# PiZero2.net
KiCad netlist of a schematic drawn in EAGLE
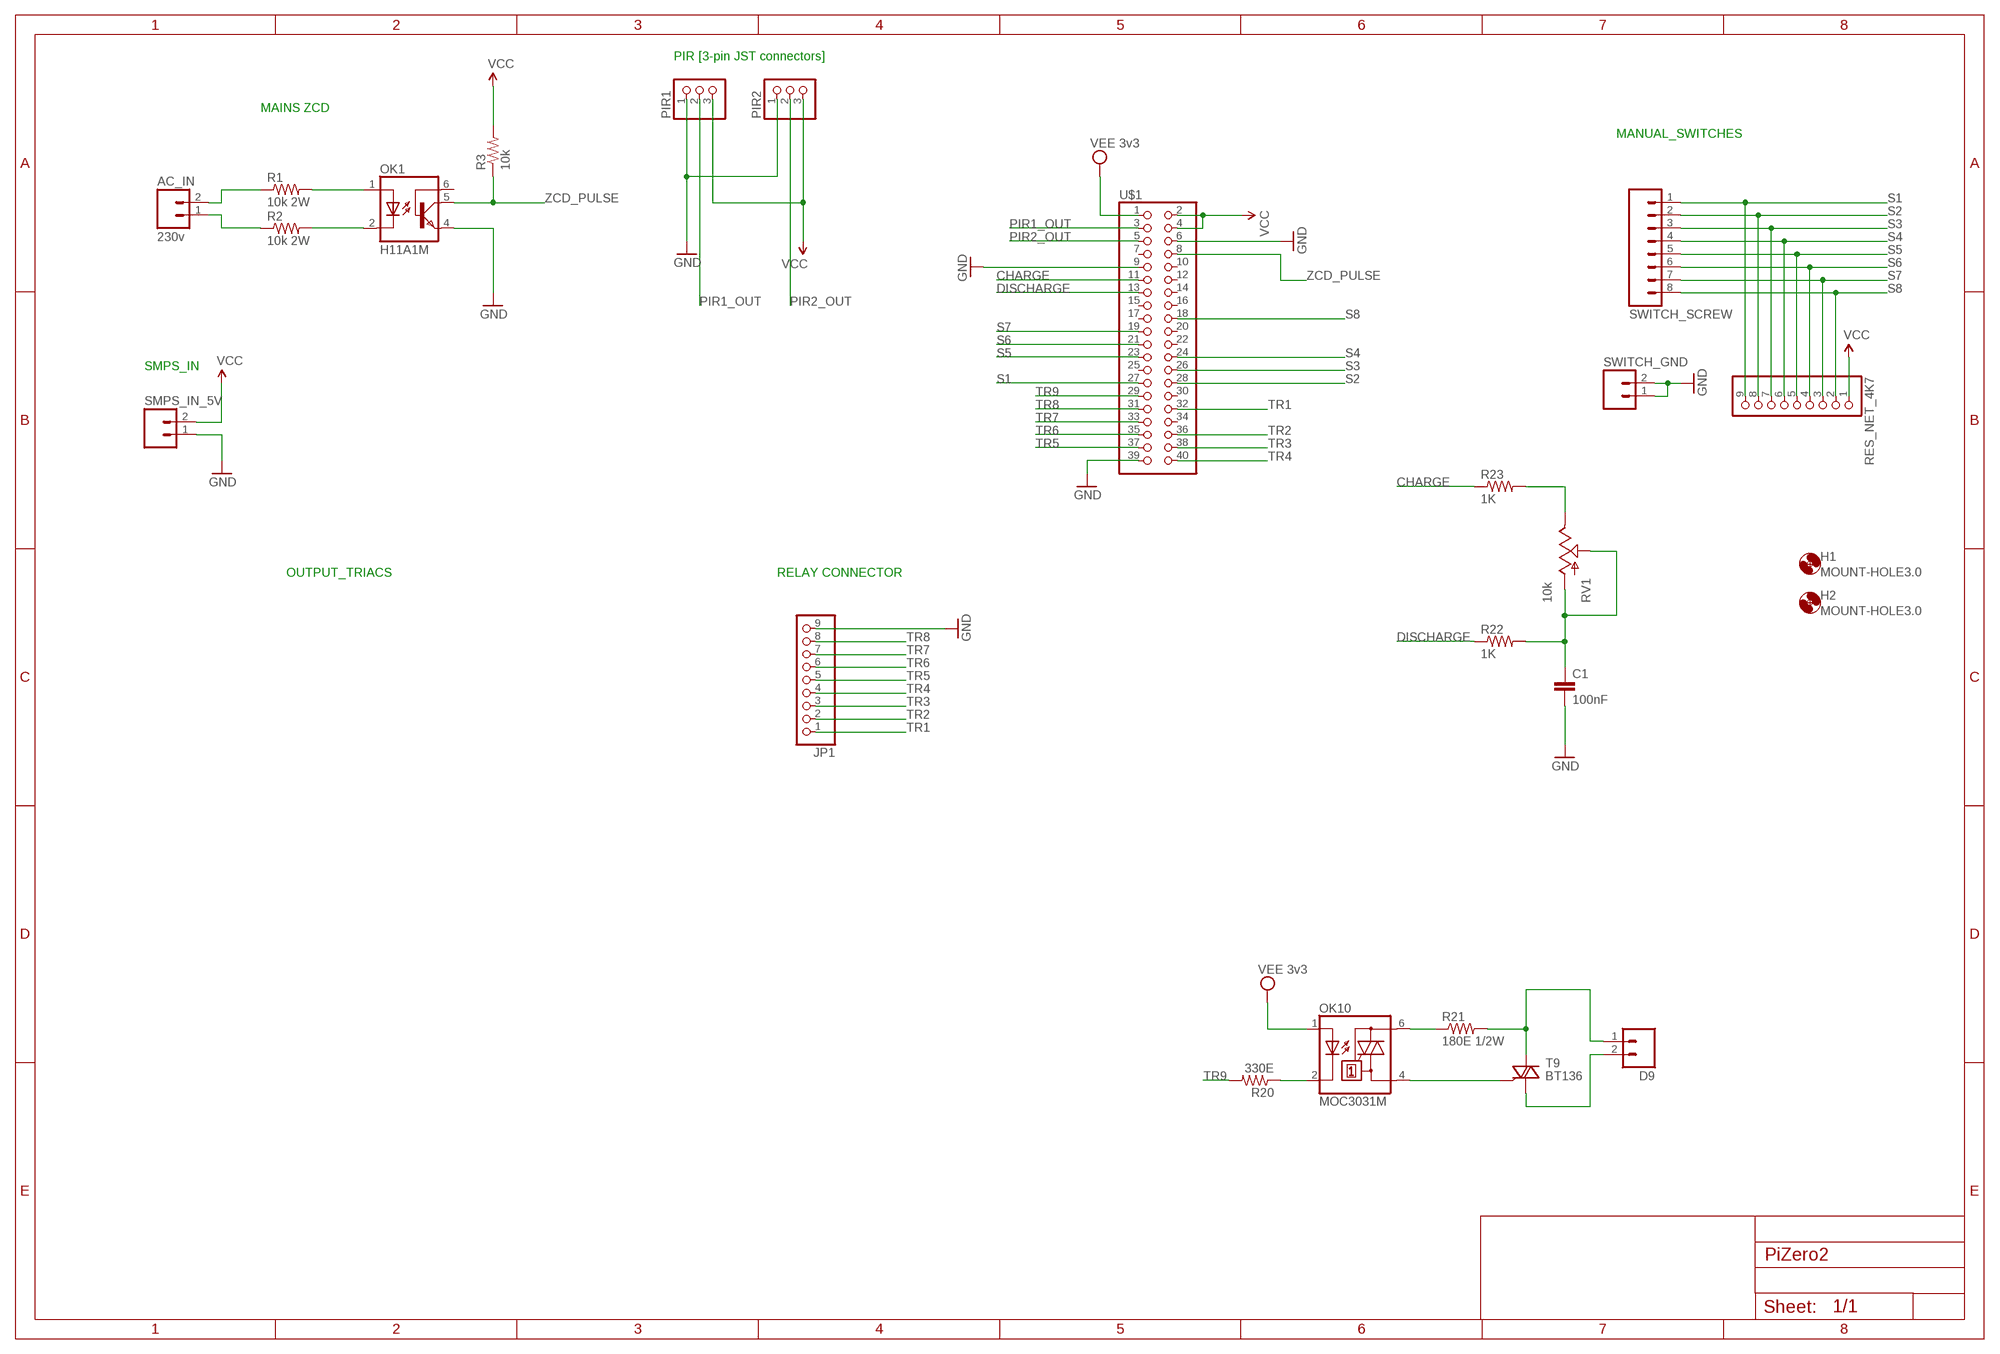
[diagram p0: schematic, sheet 1]

(export (version "E")
  (design (tool "Eeschema 10.0.6"))
  (components
    (comp (ref "AC_IN")
      (value "230v")
      (footprint "eagle-import:SCREWTERMINAL-3.5MM-2_LOCK")
      (libsource (lib "eagle-import") (part "M023.5MM_LOCK"))
    )
    (comp (ref "C1")
      (value "100nF")
      (footprint "eagle-import:C025-025X050")
      (libsource (lib "eagle-import") (part "C-EU025-025X050"))
    )
    (comp (ref "D9")
      (value "M023.5MM_LOCK")
      (footprint "eagle-import:SCREWTERMINAL-3.5MM-2_LOCK")
      (libsource (lib "eagle-import") (part "M023.5MM_LOCK"))
    )
    (comp (ref "H1")
      (value "MOUNT-HOLE3.0")
      (footprint "eagle-import:3,0")
      (libsource (lib "eagle-import") (part "MOUNT-HOLE3.0"))
    )
    (comp (ref "H2")
      (value "MOUNT-HOLE3.0")
      (footprint "eagle-import:3,0")
      (libsource (lib "eagle-import") (part "MOUNT-HOLE3.0"))
    )
    (comp (ref "JP1")
      (value "PINHD-1X9/90")
      (footprint "eagle-import:1X09_90")
      (libsource (lib "eagle-import") (part "PINHD-1X9/90"))
    )
    (comp (ref "OK1")
      (value "H11A1M")
      (footprint "eagle-import:DIL06")
      (fields (field (name "MPN") "H11A1-M"))
      (libsource (lib "eagle-import") (part "H11A?M1"))
    )
    (comp (ref "OK10")
      (value "MOC3031M")
      (footprint "eagle-import:DIL06")
      (fields (field (name "MF") "FAIRCHILD SEMICONDUCTOR"))
      (libsource (lib "eagle-import") (part "MOC3031M"))
    )
    (comp (ref "PIR1")
      (value "PINHD-1X3")
      (footprint "eagle-import:1X03")
      (libsource (lib "eagle-import") (part "PINHD-1X3"))
    )
    (comp (ref "PIR2")
      (value "PINHD-1X3")
      (footprint "eagle-import:1X03")
      (libsource (lib "eagle-import") (part "PINHD-1X3"))
    )
    (comp (ref "R1")
      (value "10k 2W")
      (footprint "eagle-import:AXIAL-0.8")
      (libsource (lib "eagle-import") (part "RESISTORPTH-2W"))
    )
    (comp (ref "R2")
      (value "10k 2W")
      (footprint "eagle-import:AXIAL-0.8")
      (libsource (lib "eagle-import") (part "RESISTORPTH-2W"))
    )
    (comp (ref "R3")
      (value "10k")
      (footprint "eagle-import:AXIAL-0.4")
      (libsource (lib "eagle-import") (part "RESISTORPTH-1/4W"))
    )
    (comp (ref "R20")
      (value "330E")
      (footprint "eagle-import:AXIAL-0.4")
      (libsource (lib "eagle-import") (part "RESISTORPTH-1/4W"))
    )
    (comp (ref "R21")
      (value "180E 1/2W")
      (footprint "eagle-import:AXIAL-0.5")
      (libsource (lib "eagle-import") (part "RESISTORPTH-1/2W"))
    )
    (comp (ref "R22")
      (value "1K")
      (footprint "eagle-import:AXIAL-0.4")
      (libsource (lib "eagle-import") (part "RESISTORPTH-1/4W"))
    )
    (comp (ref "R23")
      (value "1K")
      (footprint "eagle-import:AXIAL-0.4")
      (libsource (lib "eagle-import") (part "RESISTORPTH-1/4W"))
    )
    (comp (ref "RES_NET_4K7")
      (value "PINHD-1X9")
      (footprint "eagle-import:1X09")
      (libsource (lib "eagle-import") (part "PINHD-1X9"))
    )
    (comp (ref "RV1")
      (value "10k")
      (footprint "eagle-import:3362U")
      (libsource (lib "eagle-import") (part "POT100K_3362U"))
    )
    (comp (ref "SMPS_IN_5V")
      (value "M023.5MM_LOCK")
      (footprint "eagle-import:SCREWTERMINAL-3.5MM-2_LOCK")
      (libsource (lib "eagle-import") (part "M023.5MM_LOCK"))
    )
    (comp (ref "SWITCH_GND")
      (value "M023.5MM")
      (footprint "eagle-import:SCREWTERMINAL-3.5MM-2")
      (libsource (lib "eagle-import") (part "M023.5MM"))
    )
    (comp (ref "SWITCH_SCREW")
      (value "M083.5MM-8")
      (footprint "eagle-import:SCREWTERMINAL-3.5MM-8")
      (libsource (lib "eagle-import") (part "M083.5MM-8"))
    )
    (comp (ref "T9")
      (value "BT136")
      (footprint "eagle-import:TO220AB")
      (libsource (lib "eagle-import") (part "BT136"))
    )
    (comp (ref "U$1")
      (value "PINHD-2X20")
      (footprint "eagle-import:2X20")
      (libsource (lib "eagle-import") (part "PINHD-2X20"))
    )
  )
  (nets
    (net (code "1") (name "/CHARGE") (class "Default")
      (node (ref "R23") (pin "P$1") (pinfunction "1_P$1") (pintype "passive"))
      (node (ref "U$1") (pin "11") (pinfunction "11_11") (pintype "passive"))
    )
    (net (code "2") (name "/DISCHARGE") (class "Default")
      (node (ref "R22") (pin "P$1") (pinfunction "1_P$1") (pintype "passive"))
      (node (ref "U$1") (pin "13") (pinfunction "13_13") (pintype "passive"))
    )
    (net (code "3") (name "/PIR1_OUT") (class "Default")
      (node (ref "PIR1") (pin "2") (pinfunction "2_2") (pintype "passive"))
      (node (ref "U$1") (pin "3") (pinfunction "3_3") (pintype "passive"))
    )
    (net (code "4") (name "/PIR2_OUT") (class "Default")
      (node (ref "PIR2") (pin "2") (pinfunction "2_2") (pintype "passive"))
      (node (ref "U$1") (pin "5") (pinfunction "5_5") (pintype "passive"))
    )
    (net (code "5") (name "/S1") (class "Default")
      (node (ref "RES_NET_4K7") (pin "9") (pinfunction "9_9") (pintype "passive"))
      (node (ref "SWITCH_SCREW") (pin "1") (pinfunction "1_1") (pintype "passive"))
      (node (ref "U$1") (pin "27") (pinfunction "27_27") (pintype "passive"))
    )
    (net (code "6") (name "/S2") (class "Default")
      (node (ref "RES_NET_4K7") (pin "8") (pinfunction "8_8") (pintype "passive"))
      (node (ref "SWITCH_SCREW") (pin "2") (pinfunction "2_2") (pintype "passive"))
      (node (ref "U$1") (pin "28") (pinfunction "28_28") (pintype "passive"))
    )
    (net (code "7") (name "/S3") (class "Default")
      (node (ref "RES_NET_4K7") (pin "7") (pinfunction "7_7") (pintype "passive"))
      (node (ref "SWITCH_SCREW") (pin "3") (pinfunction "3_3") (pintype "passive"))
      (node (ref "U$1") (pin "26") (pinfunction "26_26") (pintype "passive"))
    )
    (net (code "8") (name "/S4") (class "Default")
      (node (ref "RES_NET_4K7") (pin "6") (pinfunction "6_6") (pintype "passive"))
      (node (ref "SWITCH_SCREW") (pin "4") (pinfunction "4_4") (pintype "passive"))
      (node (ref "U$1") (pin "24") (pinfunction "24_24") (pintype "passive"))
    )
    (net (code "9") (name "/S5") (class "Default")
      (node (ref "RES_NET_4K7") (pin "5") (pinfunction "5_5") (pintype "passive"))
      (node (ref "SWITCH_SCREW") (pin "5") (pinfunction "5_5") (pintype "passive"))
      (node (ref "U$1") (pin "23") (pinfunction "23_23") (pintype "passive"))
    )
    (net (code "10") (name "/S6") (class "Default")
      (node (ref "RES_NET_4K7") (pin "4") (pinfunction "4_4") (pintype "passive"))
      (node (ref "SWITCH_SCREW") (pin "6") (pinfunction "6_6") (pintype "passive"))
      (node (ref "U$1") (pin "21") (pinfunction "21_21") (pintype "passive"))
    )
    (net (code "11") (name "/S7") (class "Default")
      (node (ref "RES_NET_4K7") (pin "3") (pinfunction "3_3") (pintype "passive"))
      (node (ref "SWITCH_SCREW") (pin "7") (pinfunction "7_7") (pintype "passive"))
      (node (ref "U$1") (pin "19") (pinfunction "19_19") (pintype "passive"))
    )
    (net (code "12") (name "/S8") (class "Default")
      (node (ref "RES_NET_4K7") (pin "2") (pinfunction "2_2") (pintype "passive"))
      (node (ref "SWITCH_SCREW") (pin "8") (pinfunction "8_8") (pintype "passive"))
      (node (ref "U$1") (pin "18") (pinfunction "18_18") (pintype "passive"))
    )
    (net (code "13") (name "/TR1") (class "Default")
      (node (ref "JP1") (pin "1") (pinfunction "1_1") (pintype "passive"))
      (node (ref "U$1") (pin "32") (pinfunction "32_32") (pintype "passive"))
    )
    (net (code "14") (name "/TR2") (class "Default")
      (node (ref "JP1") (pin "2") (pinfunction "2_2") (pintype "passive"))
      (node (ref "U$1") (pin "36") (pinfunction "36_36") (pintype "passive"))
    )
    (net (code "15") (name "/TR3") (class "Default")
      (node (ref "JP1") (pin "3") (pinfunction "3_3") (pintype "passive"))
      (node (ref "U$1") (pin "38") (pinfunction "38_38") (pintype "passive"))
    )
    (net (code "16") (name "/TR4") (class "Default")
      (node (ref "JP1") (pin "4") (pinfunction "4_4") (pintype "passive"))
      (node (ref "U$1") (pin "40") (pinfunction "40_40") (pintype "passive"))
    )
    (net (code "17") (name "/TR5") (class "Default")
      (node (ref "JP1") (pin "5") (pinfunction "5_5") (pintype "passive"))
      (node (ref "U$1") (pin "37") (pinfunction "37_37") (pintype "passive"))
    )
    (net (code "18") (name "/TR6") (class "Default")
      (node (ref "JP1") (pin "6") (pinfunction "6_6") (pintype "passive"))
      (node (ref "U$1") (pin "35") (pinfunction "35_35") (pintype "passive"))
    )
    (net (code "19") (name "/TR7") (class "Default")
      (node (ref "JP1") (pin "7") (pinfunction "7_7") (pintype "passive"))
      (node (ref "U$1") (pin "33") (pinfunction "33_33") (pintype "passive"))
    )
    (net (code "20") (name "/TR8") (class "Default")
      (node (ref "JP1") (pin "8") (pinfunction "8_8") (pintype "passive"))
      (node (ref "U$1") (pin "31") (pinfunction "31_31") (pintype "passive"))
    )
    (net (code "21") (name "/TR9") (class "Default")
      (node (ref "R20") (pin "P$2") (pinfunction "2_P$2") (pintype "passive"))
      (node (ref "U$1") (pin "29") (pinfunction "29_29") (pintype "passive"))
    )
    (net (code "22") (name "/ZCD_PULSE") (class "Default")
      (node (ref "OK1") (pin "5") (pinfunction "COL_5") (pintype "passive"))
      (node (ref "R3") (pin "P$1") (pinfunction "1_P$1") (pintype "passive"))
      (node (ref "U$1") (pin "8") (pinfunction "8_8") (pintype "passive"))
    )
    (net (code "23") (name "GND") (class "Default")
      (node (ref "C1") (pin "2") (pinfunction "2_2") (pintype "passive"))
      (node (ref "JP1") (pin "9") (pinfunction "9_9") (pintype "passive"))
      (node (ref "OK1") (pin "4") (pinfunction "EMI_4") (pintype "passive"))
      (node (ref "PIR1") (pin "1") (pinfunction "1_1") (pintype "passive"))
      (node (ref "PIR2") (pin "1") (pinfunction "1_1") (pintype "passive"))
      (node (ref "SMPS_IN_5V") (pin "1") (pinfunction "1_1") (pintype "passive"))
      (node (ref "SWITCH_GND") (pin "1") (pinfunction "1_1") (pintype "passive"))
      (node (ref "SWITCH_GND") (pin "2") (pinfunction "2_2") (pintype "passive"))
      (node (ref "U$1") (pin "39") (pinfunction "39_39") (pintype "passive"))
      (node (ref "U$1") (pin "6") (pinfunction "6_6") (pintype "passive"))
      (node (ref "U$1") (pin "9") (pinfunction "9_9") (pintype "passive"))
    )
    (net (code "24") (name "Net-(OK1-A)") (class "Default")
      (node (ref "OK1") (pin "1") (pinfunction "A_1") (pintype "passive"))
      (node (ref "R1") (pin "P$2") (pinfunction "2_P$2") (pintype "passive"))
    )
    (net (code "25") (name "Net-(OK1-C)") (class "Default")
      (node (ref "OK1") (pin "2") (pinfunction "C_2") (pintype "passive"))
      (node (ref "R2") (pin "P$2") (pinfunction "2_P$2") (pintype "passive"))
    )
    (net (code "26") (name "Net-(OK10-A1)") (class "Default")
      (node (ref "OK10") (pin "4") (pinfunction "A1_4") (pintype "passive"))
      (node (ref "T9") (pin "3") (pinfunction "G_3") (pintype "passive"))
    )
    (net (code "27") (name "Net-(OK10-A2)") (class "Default")
      (node (ref "OK10") (pin "6") (pinfunction "A2_6") (pintype "passive"))
      (node (ref "R21") (pin "P$1") (pinfunction "1_P$1") (pintype "passive"))
    )
    (net (code "28") (name "Net-(OK10-C)") (class "Default")
      (node (ref "OK10") (pin "2") (pinfunction "C_2") (pintype "passive"))
      (node (ref "R20") (pin "P$1") (pinfunction "1_P$1") (pintype "passive"))
    )
    (net (code "29") (name "Net-(R1-1)") (class "Default")
      (node (ref "AC_IN") (pin "2") (pinfunction "2_2") (pintype "passive"))
      (node (ref "R1") (pin "P$1") (pinfunction "1_P$1") (pintype "passive"))
    )
    (net (code "30") (name "Net-(R2-1)") (class "Default")
      (node (ref "AC_IN") (pin "1") (pinfunction "1_1") (pintype "passive"))
      (node (ref "R2") (pin "P$1") (pinfunction "1_P$1") (pintype "passive"))
    )
    (net (code "31") (name "Net-(R21-2)") (class "Default")
      (node (ref "D9") (pin "1") (pinfunction "1_1") (pintype "passive"))
      (node (ref "R21") (pin "P$2") (pinfunction "2_P$2") (pintype "passive"))
      (node (ref "T9") (pin "2") (pinfunction "A2_2") (pintype "passive"))
    )
    (net (code "32") (name "Net-(R22-2)") (class "Default")
      (node (ref "C1") (pin "1") (pinfunction "1_1") (pintype "passive"))
      (node (ref "R22") (pin "P$2") (pinfunction "2_P$2") (pintype "passive"))
      (node (ref "RV1") (pin "P$2") (pinfunction "S_P$2") (pintype "passive"))
      (node (ref "RV1") (pin "P$3") (pinfunction "A_P$3") (pintype "passive"))
    )
    (net (code "33") (name "Net-(R23-2)") (class "Default")
      (node (ref "R23") (pin "P$2") (pinfunction "2_P$2") (pintype "passive"))
      (node (ref "RV1") (pin "P$1") (pinfunction "E_P$1") (pintype "passive"))
    )
    (net (code "34") (name "Net-(T9-A1)") (class "Default")
      (node (ref "D9") (pin "2") (pinfunction "2_2") (pintype "passive"))
      (node (ref "T9") (pin "1") (pinfunction "A1_1") (pintype "passive"))
    )
    (net (code "35") (name "VCC") (class "Default")
      (node (ref "PIR1") (pin "3") (pinfunction "3_3") (pintype "passive"))
      (node (ref "PIR2") (pin "3") (pinfunction "3_3") (pintype "passive"))
      (node (ref "R3") (pin "P$2") (pinfunction "2_P$2") (pintype "passive"))
      (node (ref "RES_NET_4K7") (pin "1") (pinfunction "1_1") (pintype "passive"))
      (node (ref "SMPS_IN_5V") (pin "2") (pinfunction "2_2") (pintype "passive"))
      (node (ref "U$1") (pin "2") (pinfunction "2_2") (pintype "passive"))
      (node (ref "U$1") (pin "4") (pinfunction "4_4") (pintype "passive"))
    )
    (net (code "36") (name "VEE 3v3") (class "Default")
      (node (ref "OK10") (pin "1") (pinfunction "A_1") (pintype "passive"))
      (node (ref "U$1") (pin "1") (pinfunction "1_1") (pintype "passive"))
    )
    (net (code "37") (name "unconnected-(OK1-BAS-Pad6)") (class "Default")
      (node (ref "OK1") (pin "6") (pinfunction "BAS_6") (pintype "passive"))
    )
    (net (code "38") (name "unconnected-(U$1-Pad7)") (class "Default")
      (node (ref "U$1") (pin "7") (pinfunction "7_7") (pintype "passive"))
    )
    (net (code "39") (name "unconnected-(U$1-Pad10)") (class "Default")
      (node (ref "U$1") (pin "10") (pinfunction "10_10") (pintype "passive"))
    )
    (net (code "40") (name "unconnected-(U$1-Pad12)") (class "Default")
      (node (ref "U$1") (pin "12") (pinfunction "12_12") (pintype "passive"))
    )
    (net (code "41") (name "unconnected-(U$1-Pad14)") (class "Default")
      (node (ref "U$1") (pin "14") (pinfunction "14_14") (pintype "passive"))
    )
    (net (code "42") (name "unconnected-(U$1-Pad15)") (class "Default")
      (node (ref "U$1") (pin "15") (pinfunction "15_15") (pintype "passive"))
    )
    (net (code "43") (name "unconnected-(U$1-Pad16)") (class "Default")
      (node (ref "U$1") (pin "16") (pinfunction "16_16") (pintype "passive"))
    )
    (net (code "44") (name "unconnected-(U$1-Pad17)") (class "Default")
      (node (ref "U$1") (pin "17") (pinfunction "17_17") (pintype "passive"))
    )
    (net (code "45") (name "unconnected-(U$1-Pad20)") (class "Default")
      (node (ref "U$1") (pin "20") (pinfunction "20_20") (pintype "passive"))
    )
    (net (code "46") (name "unconnected-(U$1-Pad22)") (class "Default")
      (node (ref "U$1") (pin "22") (pinfunction "22_22") (pintype "passive"))
    )
    (net (code "47") (name "unconnected-(U$1-Pad25)") (class "Default")
      (node (ref "U$1") (pin "25") (pinfunction "25_25") (pintype "passive"))
    )
    (net (code "48") (name "unconnected-(U$1-Pad30)") (class "Default")
      (node (ref "U$1") (pin "30") (pinfunction "30_30") (pintype "passive"))
    )
    (net (code "49") (name "unconnected-(U$1-Pad34)") (class "Default")
      (node (ref "U$1") (pin "34") (pinfunction "34_34") (pintype "passive"))
    )
  )
)
